# hs-256-expansion-long-range.net
KiCad netlist of a schematic drawn in EAGLE
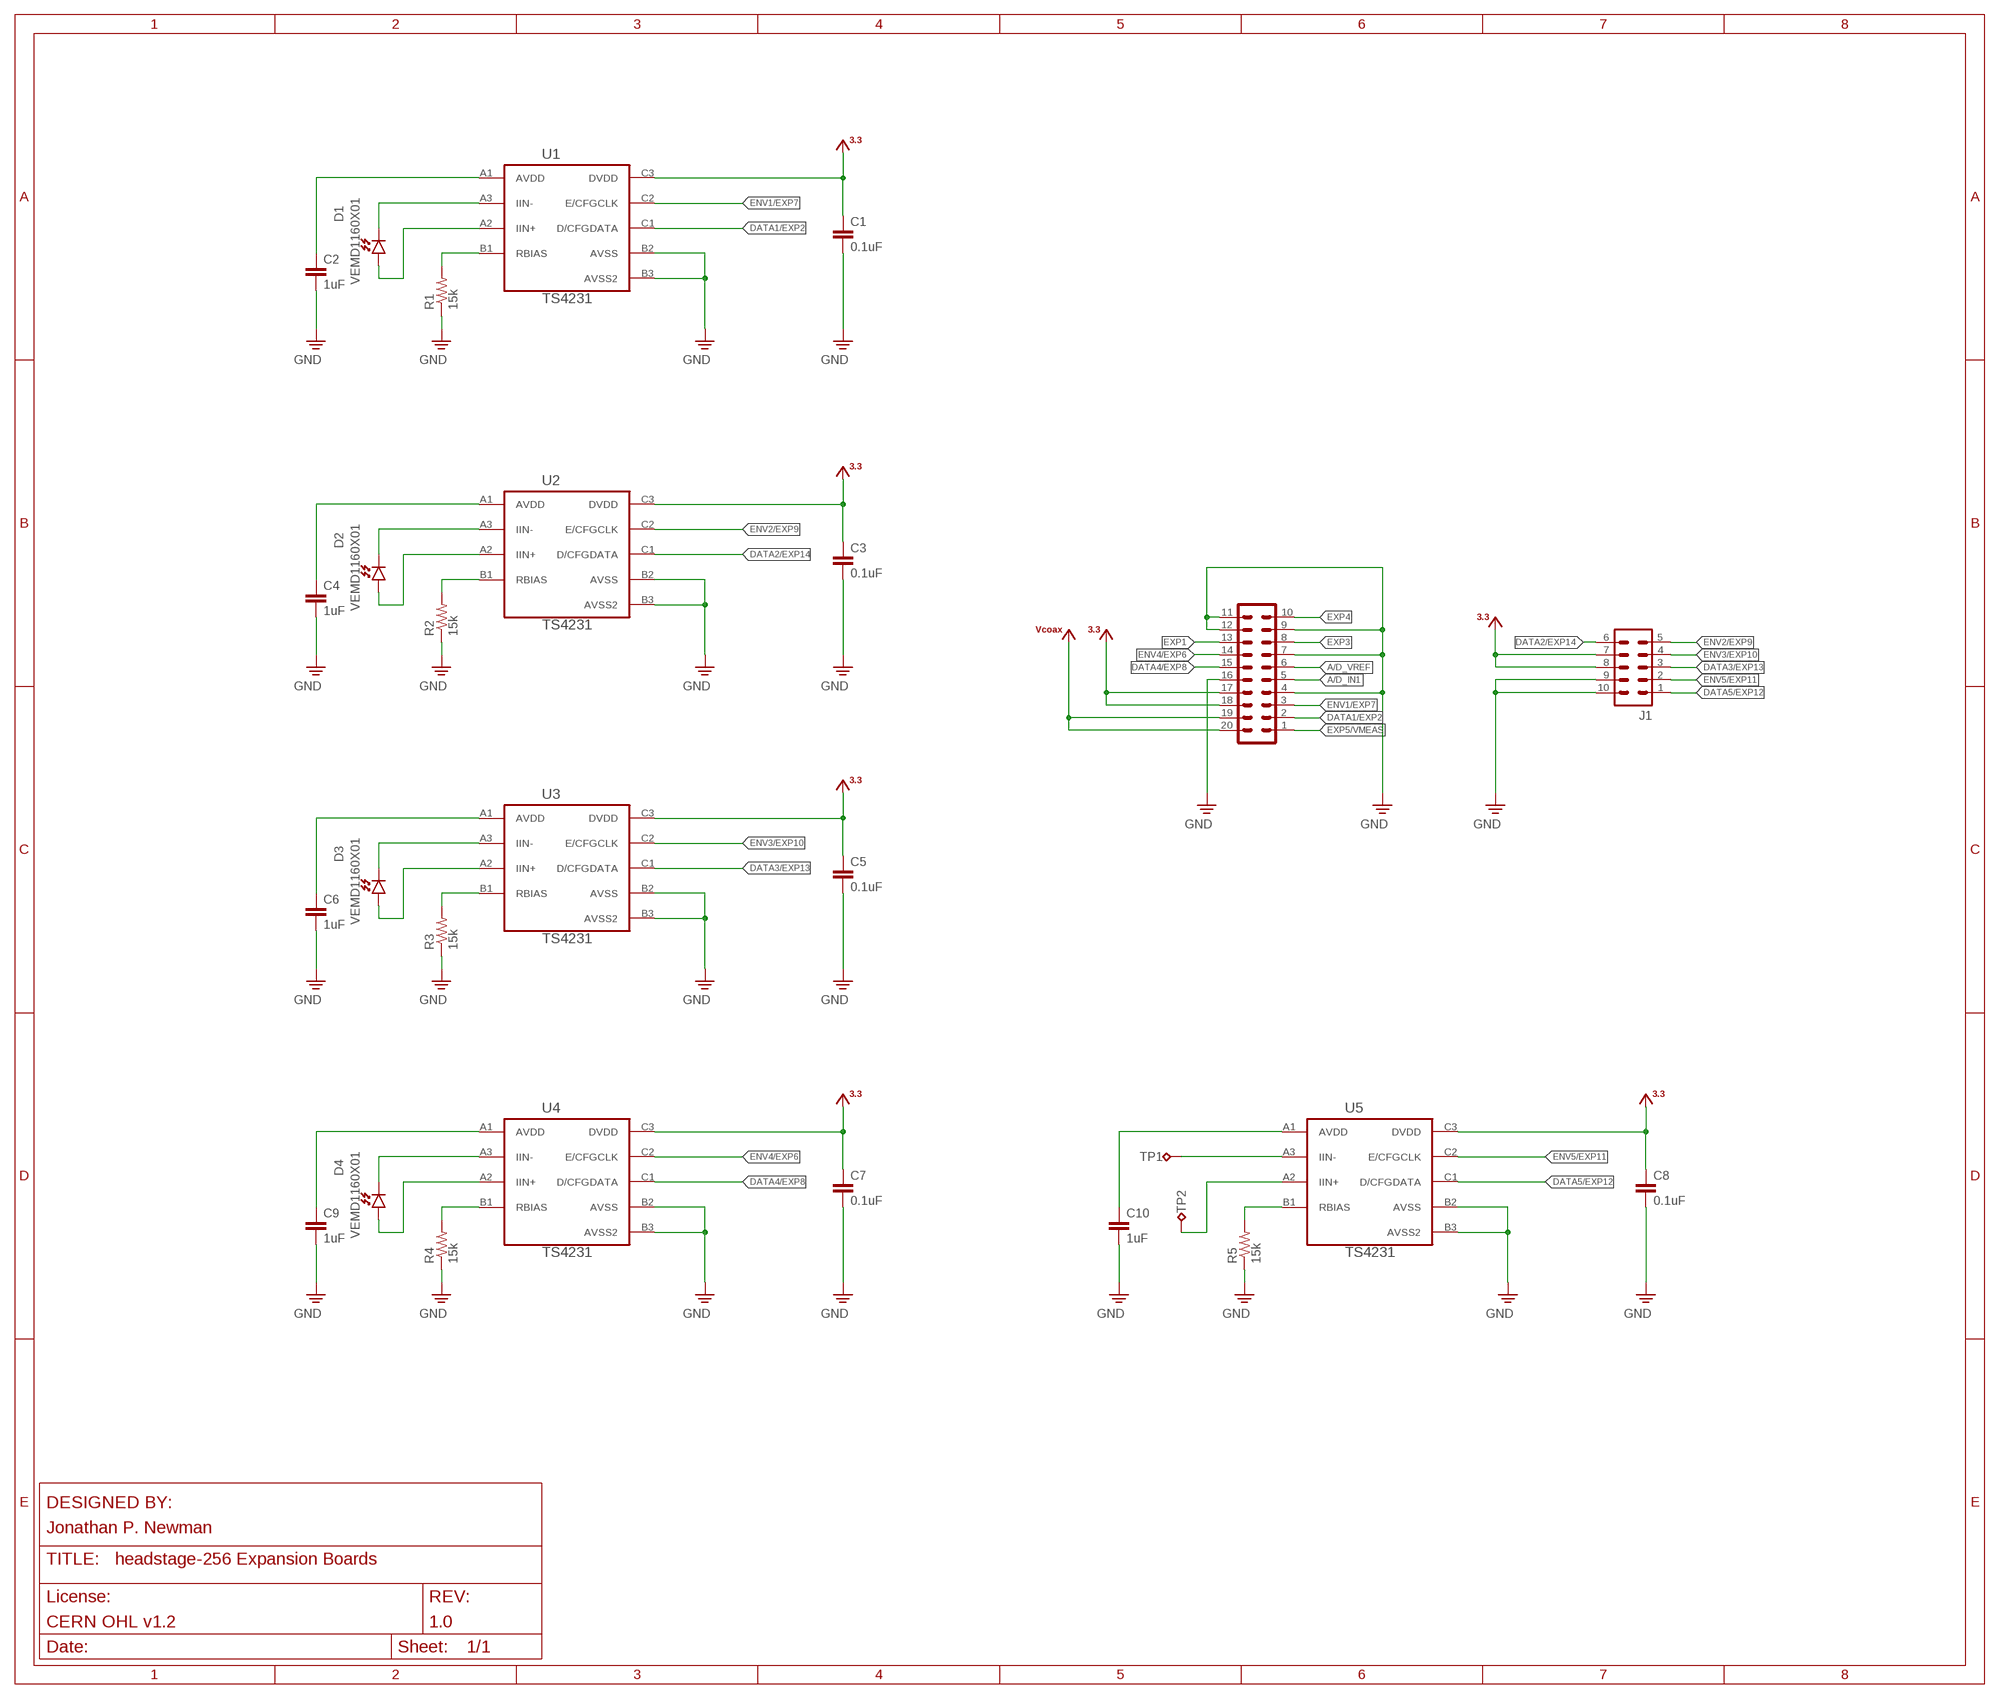
[diagram p0: schematic, sheet 1]

(export (version "E")
  (design (tool "Eeschema 10.0.6"))
  (components
    (comp (ref "C1")
      (value "0.1uF")
      (footprint "eagle-import:0201")
      (fields (field (name "PARTNO") "C0603X5R1C104K030BC"))
      (libsource (lib "eagle-import") (part "C_0201"))
    )
    (comp (ref "C2")
      (value "1uF")
      (footprint "eagle-import:0201")
      (fields (field (name "PARTNO") "CL03A105MP3ZSNH"))
      (libsource (lib "eagle-import") (part "C_0201"))
    )
    (comp (ref "C3")
      (value "0.1uF")
      (footprint "eagle-import:0201")
      (fields (field (name "PARTNO") "C0603X5R1C104K030BC"))
      (libsource (lib "eagle-import") (part "C_0201"))
    )
    (comp (ref "C4")
      (value "1uF")
      (footprint "eagle-import:0201")
      (fields (field (name "PARTNO") "CL03A105MP3ZSNH"))
      (libsource (lib "eagle-import") (part "C_0201"))
    )
    (comp (ref "C5")
      (value "0.1uF")
      (footprint "eagle-import:0201")
      (fields (field (name "PARTNO") "C0603X5R1C104K030BC"))
      (libsource (lib "eagle-import") (part "C_0201"))
    )
    (comp (ref "C6")
      (value "1uF")
      (footprint "eagle-import:0201")
      (fields (field (name "PARTNO") "CL03A105MP3ZSNH"))
      (libsource (lib "eagle-import") (part "C_0201"))
    )
    (comp (ref "C7")
      (value "0.1uF")
      (footprint "eagle-import:0201")
      (fields (field (name "PARTNO") "C0603X5R1C104K030BC"))
      (libsource (lib "eagle-import") (part "C_0201"))
    )
    (comp (ref "C8")
      (value "0.1uF")
      (footprint "eagle-import:0201")
      (fields (field (name "PARTNO") "C0603X5R1C104K030BC"))
      (libsource (lib "eagle-import") (part "C_0201"))
    )
    (comp (ref "C9")
      (value "1uF")
      (footprint "eagle-import:0201")
      (fields (field (name "PARTNO") "CL03A105MP3ZSNH"))
      (libsource (lib "eagle-import") (part "C_0201"))
    )
    (comp (ref "C10")
      (value "1uF")
      (footprint "eagle-import:0201")
      (fields (field (name "PARTNO") "CL03A105MP3ZSNH"))
      (libsource (lib "eagle-import") (part "C_0201"))
    )
    (comp (ref "D1")
      (value "VEMD1160X01")
      (footprint "eagle-import:SFH2400FA")
      (libsource (lib "eagle-import") (part "PHOTODIODE_SFH2400FA"))
    )
    (comp (ref "D2")
      (value "VEMD1160X01")
      (footprint "eagle-import:SFH2400FA")
      (libsource (lib "eagle-import") (part "PHOTODIODE_SFH2400FA"))
    )
    (comp (ref "D3")
      (value "VEMD1160X01")
      (footprint "eagle-import:SFH2400FA")
      (libsource (lib "eagle-import") (part "PHOTODIODE_SFH2400FA"))
    )
    (comp (ref "D4")
      (value "VEMD1160X01")
      (footprint "eagle-import:SFH2400FA")
      (libsource (lib "eagle-import") (part "PHOTODIODE_SFH2400FA"))
    )
    (comp (ref "J1")
      (value "PINHD-2X5_DF40-REC")
      (footprint "eagle-import:DF40-10REC")
      (libsource (lib "eagle-import") (part "PINHD-2X5_DF40-REC"))
    )
    (comp (ref "J2")
      (value "PINHD-2X10_DF40-20REC")
      (footprint "eagle-import:DF40-20REC")
      (libsource (lib "eagle-import") (part "PINHD-2X10_DF40-20REC"))
    )
    (comp (ref "R1")
      (value "15k")
      (footprint "eagle-import:0201")
      (libsource (lib "eagle-import") (part "R_0201"))
    )
    (comp (ref "R2")
      (value "15k")
      (footprint "eagle-import:0201")
      (libsource (lib "eagle-import") (part "R_0201"))
    )
    (comp (ref "R3")
      (value "15k")
      (footprint "eagle-import:0201")
      (libsource (lib "eagle-import") (part "R_0201"))
    )
    (comp (ref "R4")
      (value "15k")
      (footprint "eagle-import:0201")
      (libsource (lib "eagle-import") (part "R_0201"))
    )
    (comp (ref "R5")
      (value "15k")
      (footprint "eagle-import:0201")
      (libsource (lib "eagle-import") (part "R_0201"))
    )
    (comp (ref "TP1")
      (value "TPTP20SQ")
      (footprint "eagle-import:TP20SQ")
      (libsource (lib "eagle-import") (part "TPTP20SQ"))
    )
    (comp (ref "TP2")
      (value "TPTP20SQ")
      (footprint "eagle-import:TP20SQ")
      (libsource (lib "eagle-import") (part "TPTP20SQ"))
    )
    (comp (ref "U1")
      (value "TS4231")
      (footprint "eagle-import:WLCSP3X3")
      (libsource (lib "eagle-import") (part "TS4231"))
    )
    (comp (ref "U2")
      (value "TS4231")
      (footprint "eagle-import:WLCSP3X3")
      (libsource (lib "eagle-import") (part "TS4231"))
    )
    (comp (ref "U3")
      (value "TS4231")
      (footprint "eagle-import:WLCSP3X3")
      (libsource (lib "eagle-import") (part "TS4231"))
    )
    (comp (ref "U4")
      (value "TS4231")
      (footprint "eagle-import:WLCSP3X3")
      (libsource (lib "eagle-import") (part "TS4231"))
    )
    (comp (ref "U5")
      (value "TS4231")
      (footprint "eagle-import:WLCSP3X3")
      (libsource (lib "eagle-import") (part "TS4231"))
    )
  )
  (nets
    (net (code "1") (name "+3V3") (class "Default")
      (node (ref "C1") (pin "1") (pinfunction "1_1") (pintype "passive"))
      (node (ref "C3") (pin "1") (pinfunction "1_1") (pintype "passive"))
      (node (ref "C5") (pin "1") (pinfunction "1_1") (pintype "passive"))
      (node (ref "C7") (pin "1") (pinfunction "1_1") (pintype "passive"))
      (node (ref "C8") (pin "1") (pinfunction "1_1") (pintype "passive"))
      (node (ref "J1") (pin "7") (pinfunction "8_7") (pintype "passive"))
      (node (ref "J1") (pin "8") (pinfunction "6_8") (pintype "passive"))
      (node (ref "J2") (pin "17") (pinfunction "17_17") (pintype "bidirectional"))
      (node (ref "J2") (pin "18") (pinfunction "18_18") (pintype "bidirectional"))
      (node (ref "U1") (pin "C3") (pinfunction "DVDD_C3") (pintype "power_in"))
      (node (ref "U2") (pin "C3") (pinfunction "DVDD_C3") (pintype "power_in"))
      (node (ref "U3") (pin "C3") (pinfunction "DVDD_C3") (pintype "power_in"))
      (node (ref "U4") (pin "C3") (pinfunction "DVDD_C3") (pintype "power_in"))
      (node (ref "U5") (pin "C3") (pinfunction "DVDD_C3") (pintype "power_in"))
    )
    (net (code "2") (name "+VCOAX") (class "Default")
      (node (ref "J2") (pin "19") (pinfunction "19_19") (pintype "bidirectional"))
      (node (ref "J2") (pin "20") (pinfunction "20_20") (pintype "bidirectional"))
    )
    (net (code "3") (name "A{slash}D_IN1") (class "Default")
      (node (ref "J2") (pin "5") (pinfunction "5_5") (pintype "bidirectional"))
    )
    (net (code "4") (name "A{slash}D_VREF") (class "Default")
      (node (ref "J2") (pin "6") (pinfunction "6_6") (pintype "bidirectional"))
    )
    (net (code "5") (name "DATA1{slash}EXP2") (class "Default")
      (node (ref "J2") (pin "2") (pinfunction "2_2") (pintype "bidirectional"))
      (node (ref "U1") (pin "C1") (pinfunction "D/CFGDATA_C1") (pintype "bidirectional"))
    )
    (net (code "6") (name "DATA2{slash}EXP14") (class "Default")
      (node (ref "J1") (pin "6") (pinfunction "10_6") (pintype "passive"))
      (node (ref "U2") (pin "C1") (pinfunction "D/CFGDATA_C1") (pintype "bidirectional"))
    )
    (net (code "7") (name "DATA3{slash}EXP13") (class "Default")
      (node (ref "J1") (pin "3") (pinfunction "5_3") (pintype "passive"))
      (node (ref "U3") (pin "C1") (pinfunction "D/CFGDATA_C1") (pintype "bidirectional"))
    )
    (net (code "8") (name "DATA4{slash}EXP8") (class "Default")
      (node (ref "J2") (pin "15") (pinfunction "15_15") (pintype "bidirectional"))
      (node (ref "U4") (pin "C1") (pinfunction "D/CFGDATA_C1") (pintype "bidirectional"))
    )
    (net (code "9") (name "DATA5{slash}EXP12") (class "Default")
      (node (ref "J1") (pin "1") (pinfunction "1_1") (pintype "passive"))
      (node (ref "U5") (pin "C1") (pinfunction "D/CFGDATA_C1") (pintype "bidirectional"))
    )
    (net (code "10") (name "ENV1{slash}EXP7") (class "Default")
      (node (ref "J2") (pin "3") (pinfunction "3_3") (pintype "bidirectional"))
      (node (ref "U1") (pin "C2") (pinfunction "E/CFGCLK_C2") (pintype "bidirectional"))
    )
    (net (code "11") (name "ENV2{slash}EXP9") (class "Default")
      (node (ref "J1") (pin "5") (pinfunction "9_5") (pintype "passive"))
      (node (ref "U2") (pin "C2") (pinfunction "E/CFGCLK_C2") (pintype "bidirectional"))
    )
    (net (code "12") (name "ENV3{slash}EXP10") (class "Default")
      (node (ref "J1") (pin "4") (pinfunction "7_4") (pintype "passive"))
      (node (ref "U3") (pin "C2") (pinfunction "E/CFGCLK_C2") (pintype "bidirectional"))
    )
    (net (code "13") (name "ENV4{slash}EXP6") (class "Default")
      (node (ref "J2") (pin "14") (pinfunction "14_14") (pintype "bidirectional"))
      (node (ref "U4") (pin "C2") (pinfunction "E/CFGCLK_C2") (pintype "bidirectional"))
    )
    (net (code "14") (name "ENV5{slash}EXP11") (class "Default")
      (node (ref "J1") (pin "2") (pinfunction "3_2") (pintype "passive"))
      (node (ref "U5") (pin "C2") (pinfunction "E/CFGCLK_C2") (pintype "bidirectional"))
    )
    (net (code "15") (name "EXP1") (class "Default")
      (node (ref "J2") (pin "13") (pinfunction "13_13") (pintype "bidirectional"))
    )
    (net (code "16") (name "EXP3") (class "Default")
      (node (ref "J2") (pin "8") (pinfunction "8_8") (pintype "bidirectional"))
    )
    (net (code "17") (name "EXP4") (class "Default")
      (node (ref "J2") (pin "10") (pinfunction "10_10") (pintype "bidirectional"))
    )
    (net (code "18") (name "EXP5{slash}VMEAS") (class "Default")
      (node (ref "J2") (pin "1") (pinfunction "1_1") (pintype "bidirectional"))
    )
    (net (code "19") (name "GND") (class "Default")
      (node (ref "C1") (pin "2") (pinfunction "2_2") (pintype "passive"))
      (node (ref "C10") (pin "2") (pinfunction "2_2") (pintype "passive"))
      (node (ref "C2") (pin "2") (pinfunction "2_2") (pintype "passive"))
      (node (ref "C3") (pin "2") (pinfunction "2_2") (pintype "passive"))
      (node (ref "C4") (pin "2") (pinfunction "2_2") (pintype "passive"))
      (node (ref "C5") (pin "2") (pinfunction "2_2") (pintype "passive"))
      (node (ref "C6") (pin "2") (pinfunction "2_2") (pintype "passive"))
      (node (ref "C7") (pin "2") (pinfunction "2_2") (pintype "passive"))
      (node (ref "C8") (pin "2") (pinfunction "2_2") (pintype "passive"))
      (node (ref "C9") (pin "2") (pinfunction "2_2") (pintype "passive"))
      (node (ref "J1") (pin "10") (pinfunction "2_10") (pintype "passive"))
      (node (ref "J1") (pin "9") (pinfunction "4_9") (pintype "passive"))
      (node (ref "J2") (pin "11") (pinfunction "11_11") (pintype "bidirectional"))
      (node (ref "J2") (pin "12") (pinfunction "12_12") (pintype "bidirectional"))
      (node (ref "J2") (pin "16") (pinfunction "16_16") (pintype "bidirectional"))
      (node (ref "J2") (pin "4") (pinfunction "4_4") (pintype "bidirectional"))
      (node (ref "J2") (pin "7") (pinfunction "7_7") (pintype "bidirectional"))
      (node (ref "J2") (pin "9") (pinfunction "9_9") (pintype "bidirectional"))
      (node (ref "R1") (pin "1") (pinfunction "1_1") (pintype "passive"))
      (node (ref "R2") (pin "1") (pinfunction "1_1") (pintype "passive"))
      (node (ref "R3") (pin "1") (pinfunction "1_1") (pintype "passive"))
      (node (ref "R4") (pin "1") (pinfunction "1_1") (pintype "passive"))
      (node (ref "R5") (pin "1") (pinfunction "1_1") (pintype "passive"))
      (node (ref "U1") (pin "B2") (pinfunction "AVSS_B2") (pintype "passive"))
      (node (ref "U1") (pin "B3") (pinfunction "AVSS2_B3") (pintype "passive"))
      (node (ref "U2") (pin "B2") (pinfunction "AVSS_B2") (pintype "passive"))
      (node (ref "U2") (pin "B3") (pinfunction "AVSS2_B3") (pintype "passive"))
      (node (ref "U3") (pin "B2") (pinfunction "AVSS_B2") (pintype "passive"))
      (node (ref "U3") (pin "B3") (pinfunction "AVSS2_B3") (pintype "passive"))
      (node (ref "U4") (pin "B2") (pinfunction "AVSS_B2") (pintype "passive"))
      (node (ref "U4") (pin "B3") (pinfunction "AVSS2_B3") (pintype "passive"))
      (node (ref "U5") (pin "B2") (pinfunction "AVSS_B2") (pintype "passive"))
      (node (ref "U5") (pin "B3") (pinfunction "AVSS2_B3") (pintype "passive"))
    )
    (net (code "20") (name "Net-(D1-A)") (class "Default")
      (node (ref "D1") (pin "3") (pinfunction "A_3") (pintype "passive"))
      (node (ref "U1") (pin "A2") (pinfunction "IIN+_A2") (pintype "input"))
    )
    (net (code "21") (name "Net-(D1-C)") (class "Default")
      (node (ref "D1") (pin "1") (pinfunction "C_1") (pintype "passive"))
      (node (ref "U1") (pin "A3") (pinfunction "IIN-_A3") (pintype "input"))
    )
    (net (code "22") (name "Net-(D2-A)") (class "Default")
      (node (ref "D2") (pin "3") (pinfunction "A_3") (pintype "passive"))
      (node (ref "U2") (pin "A2") (pinfunction "IIN+_A2") (pintype "input"))
    )
    (net (code "23") (name "Net-(D2-C)") (class "Default")
      (node (ref "D2") (pin "1") (pinfunction "C_1") (pintype "passive"))
      (node (ref "U2") (pin "A3") (pinfunction "IIN-_A3") (pintype "input"))
    )
    (net (code "24") (name "Net-(D3-A)") (class "Default")
      (node (ref "D3") (pin "3") (pinfunction "A_3") (pintype "passive"))
      (node (ref "U3") (pin "A2") (pinfunction "IIN+_A2") (pintype "input"))
    )
    (net (code "25") (name "Net-(D3-C)") (class "Default")
      (node (ref "D3") (pin "1") (pinfunction "C_1") (pintype "passive"))
      (node (ref "U3") (pin "A3") (pinfunction "IIN-_A3") (pintype "input"))
    )
    (net (code "26") (name "Net-(D4-A)") (class "Default")
      (node (ref "D4") (pin "3") (pinfunction "A_3") (pintype "passive"))
      (node (ref "U4") (pin "A2") (pinfunction "IIN+_A2") (pintype "input"))
    )
    (net (code "27") (name "Net-(D4-C)") (class "Default")
      (node (ref "D4") (pin "1") (pinfunction "C_1") (pintype "passive"))
      (node (ref "U4") (pin "A3") (pinfunction "IIN-_A3") (pintype "input"))
    )
    (net (code "28") (name "Net-(U1-AVDD)") (class "Default")
      (node (ref "C2") (pin "1") (pinfunction "1_1") (pintype "passive"))
      (node (ref "U1") (pin "A1") (pinfunction "AVDD_A1") (pintype "passive"))
    )
    (net (code "29") (name "Net-(U1-RBIAS)") (class "Default")
      (node (ref "R1") (pin "2") (pinfunction "2_2") (pintype "passive"))
      (node (ref "U1") (pin "B1") (pinfunction "RBIAS_B1") (pintype "passive"))
    )
    (net (code "30") (name "Net-(U2-AVDD)") (class "Default")
      (node (ref "C4") (pin "1") (pinfunction "1_1") (pintype "passive"))
      (node (ref "U2") (pin "A1") (pinfunction "AVDD_A1") (pintype "passive"))
    )
    (net (code "31") (name "Net-(U2-RBIAS)") (class "Default")
      (node (ref "R2") (pin "2") (pinfunction "2_2") (pintype "passive"))
      (node (ref "U2") (pin "B1") (pinfunction "RBIAS_B1") (pintype "passive"))
    )
    (net (code "32") (name "Net-(U3-AVDD)") (class "Default")
      (node (ref "C6") (pin "1") (pinfunction "1_1") (pintype "passive"))
      (node (ref "U3") (pin "A1") (pinfunction "AVDD_A1") (pintype "passive"))
    )
    (net (code "33") (name "Net-(U3-RBIAS)") (class "Default")
      (node (ref "R3") (pin "2") (pinfunction "2_2") (pintype "passive"))
      (node (ref "U3") (pin "B1") (pinfunction "RBIAS_B1") (pintype "passive"))
    )
    (net (code "34") (name "Net-(U4-AVDD)") (class "Default")
      (node (ref "C9") (pin "1") (pinfunction "1_1") (pintype "passive"))
      (node (ref "U4") (pin "A1") (pinfunction "AVDD_A1") (pintype "passive"))
    )
    (net (code "35") (name "Net-(U4-RBIAS)") (class "Default")
      (node (ref "R4") (pin "2") (pinfunction "2_2") (pintype "passive"))
      (node (ref "U4") (pin "B1") (pinfunction "RBIAS_B1") (pintype "passive"))
    )
    (net (code "36") (name "Net-(U5-AVDD)") (class "Default")
      (node (ref "C10") (pin "1") (pinfunction "1_1") (pintype "passive"))
      (node (ref "U5") (pin "A1") (pinfunction "AVDD_A1") (pintype "passive"))
    )
    (net (code "37") (name "Net-(U5-IIN+)") (class "Default")
      (node (ref "TP2") (pin "TP") (pinfunction "TP_TP") (pintype "bidirectional"))
      (node (ref "U5") (pin "A2") (pinfunction "IIN+_A2") (pintype "input"))
    )
    (net (code "38") (name "Net-(U5-IIN-)") (class "Default")
      (node (ref "TP1") (pin "TP") (pinfunction "TP_TP") (pintype "bidirectional"))
      (node (ref "U5") (pin "A3") (pinfunction "IIN-_A3") (pintype "input"))
    )
    (net (code "39") (name "Net-(U5-RBIAS)") (class "Default")
      (node (ref "R5") (pin "2") (pinfunction "2_2") (pintype "passive"))
      (node (ref "U5") (pin "B1") (pinfunction "RBIAS_B1") (pintype "passive"))
    )
  )
)
